# LED_5730_2.net
KiCad netlist of a schematic drawn in Altium Designer
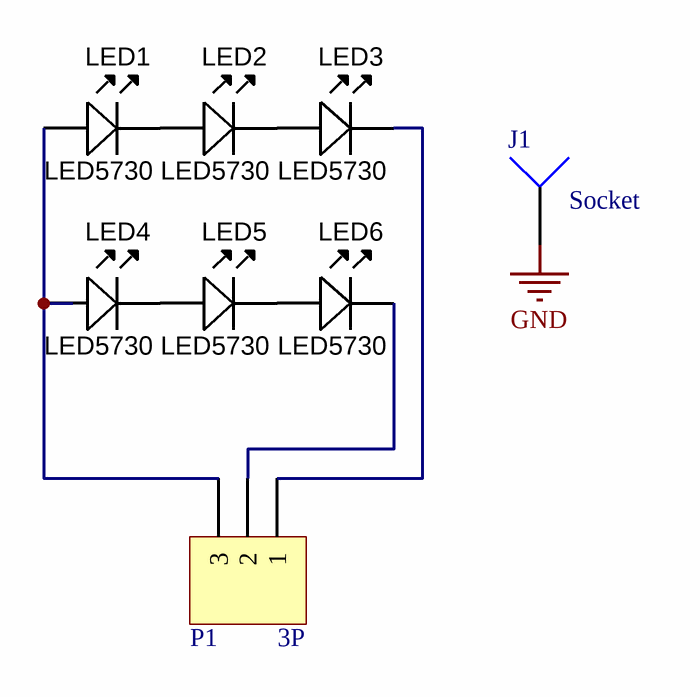
[diagram p0: LED_5730 2.SchDoc]

(export (version "E")
  (design (tool "Eeschema 10.0.6"))
  (components
    (comp (ref "J1")
      (value "Socket")
      (footprint "lobatoc")
      (fields (field (name "PUBLISHER") "Altium Limited"))
      (libsource (lib "Miscellaneous Connectors") (part "Socket"))
    )
    (comp (ref "LED1")
      (value "LED 5730 chân dán")
      (footprint "5730")
      (description "LED 0805 SMD Blue 100mcd 470nm")
      (fields (field (name "COLOR") "LED5730"))
      (libsource (lib "PBL - Light Sources") (part "LED_SMD_Blue_0805_100mcd"))
    )
    (comp (ref "LED2")
      (value "LED 5730 chân dán")
      (footprint "5730")
      (description "LED 0805 SMD Blue 100mcd 470nm")
      (fields (field (name "COLOR") "LED5730"))
      (libsource (lib "PBL - Light Sources") (part "LED_SMD_Blue_0805_100mcd"))
    )
    (comp (ref "LED3")
      (value "LED 5730 chân dán")
      (footprint "5730")
      (description "LED 0805 SMD Blue 100mcd 470nm")
      (fields (field (name "COLOR") "LED5730"))
      (libsource (lib "PBL - Light Sources") (part "LED_SMD_Blue_0805_100mcd"))
    )
    (comp (ref "LED4")
      (value "LED 5730 chân dán")
      (footprint "5730")
      (description "LED 0805 SMD Blue 100mcd 470nm")
      (fields (field (name "COLOR") "LED5730"))
      (libsource (lib "PBL - Light Sources") (part "LED_SMD_Blue_0805_100mcd"))
    )
    (comp (ref "LED5")
      (value "LED 5730 chân dán")
      (footprint "5730")
      (description "LED 0805 SMD Blue 100mcd 470nm")
      (fields (field (name "COLOR") "LED5730"))
      (libsource (lib "PBL - Light Sources") (part "LED_SMD_Blue_0805_100mcd"))
    )
    (comp (ref "LED6")
      (value "LED 5730 chân dán")
      (footprint "5730")
      (description "LED 0805 SMD Blue 100mcd 470nm")
      (fields (field (name "COLOR") "LED5730"))
      (libsource (lib "PBL - Light Sources") (part "LED_SMD_Blue_0805_100mcd"))
    )
    (comp (ref "P1")
      (value "3P")
      (footprint "HDR1X3H")
      (description "Header, 3-Pin, Right Angle")
      (fields
        (field (name "Comment") "Jump đực chân thẳng, 2.54mm 3P")
        (field (name "PUBLISHER") "Altium Limited")
      )
      (libsource (lib "Miscellaneous Connectors") (part "Header 3H"))
    )
  )
  (nets
    (net (code "1") (name "GND") (class "Default")
      (node (ref "J1") (pin "1") (pinfunction "1_1") (pintype "passive"))
    )
    (net (code "2") (name "Net-(LED1-PadA)") (class "Default")
      (node (ref "LED1") (pin "A") (pinfunction "A_A") (pintype "passive"))
      (node (ref "LED4") (pin "A") (pinfunction "A_A") (pintype "passive"))
      (node (ref "P1") (pin "3") (pinfunction "3_3") (pintype "passive"))
    )
    (net (code "3") (name "Net-(LED1-PadK)") (class "Default")
      (node (ref "LED1") (pin "K") (pinfunction "K_K") (pintype "passive"))
      (node (ref "LED2") (pin "A") (pinfunction "A_A") (pintype "passive"))
    )
    (net (code "4") (name "Net-(LED2-PadK)") (class "Default")
      (node (ref "LED2") (pin "K") (pinfunction "K_K") (pintype "passive"))
      (node (ref "LED3") (pin "A") (pinfunction "A_A") (pintype "passive"))
    )
    (net (code "5") (name "Net-(LED3-PadK)") (class "Default")
      (node (ref "LED3") (pin "K") (pinfunction "K_K") (pintype "passive"))
      (node (ref "P1") (pin "1") (pinfunction "1_1") (pintype "passive"))
    )
    (net (code "6") (name "Net-(LED4-PadK)") (class "Default")
      (node (ref "LED4") (pin "K") (pinfunction "K_K") (pintype "passive"))
      (node (ref "LED5") (pin "A") (pinfunction "A_A") (pintype "passive"))
    )
    (net (code "7") (name "Net-(LED5-PadK)") (class "Default")
      (node (ref "LED5") (pin "K") (pinfunction "K_K") (pintype "passive"))
      (node (ref "LED6") (pin "A") (pinfunction "A_A") (pintype "passive"))
    )
    (net (code "8") (name "Net-(LED6-PadK)") (class "Default")
      (node (ref "LED6") (pin "K") (pinfunction "K_K") (pintype "passive"))
      (node (ref "P1") (pin "2") (pinfunction "2_2") (pintype "passive"))
    )
  )
)
